# MINI_SAM_D51_013.net
KiCad netlist of a schematic drawn in EAGLE
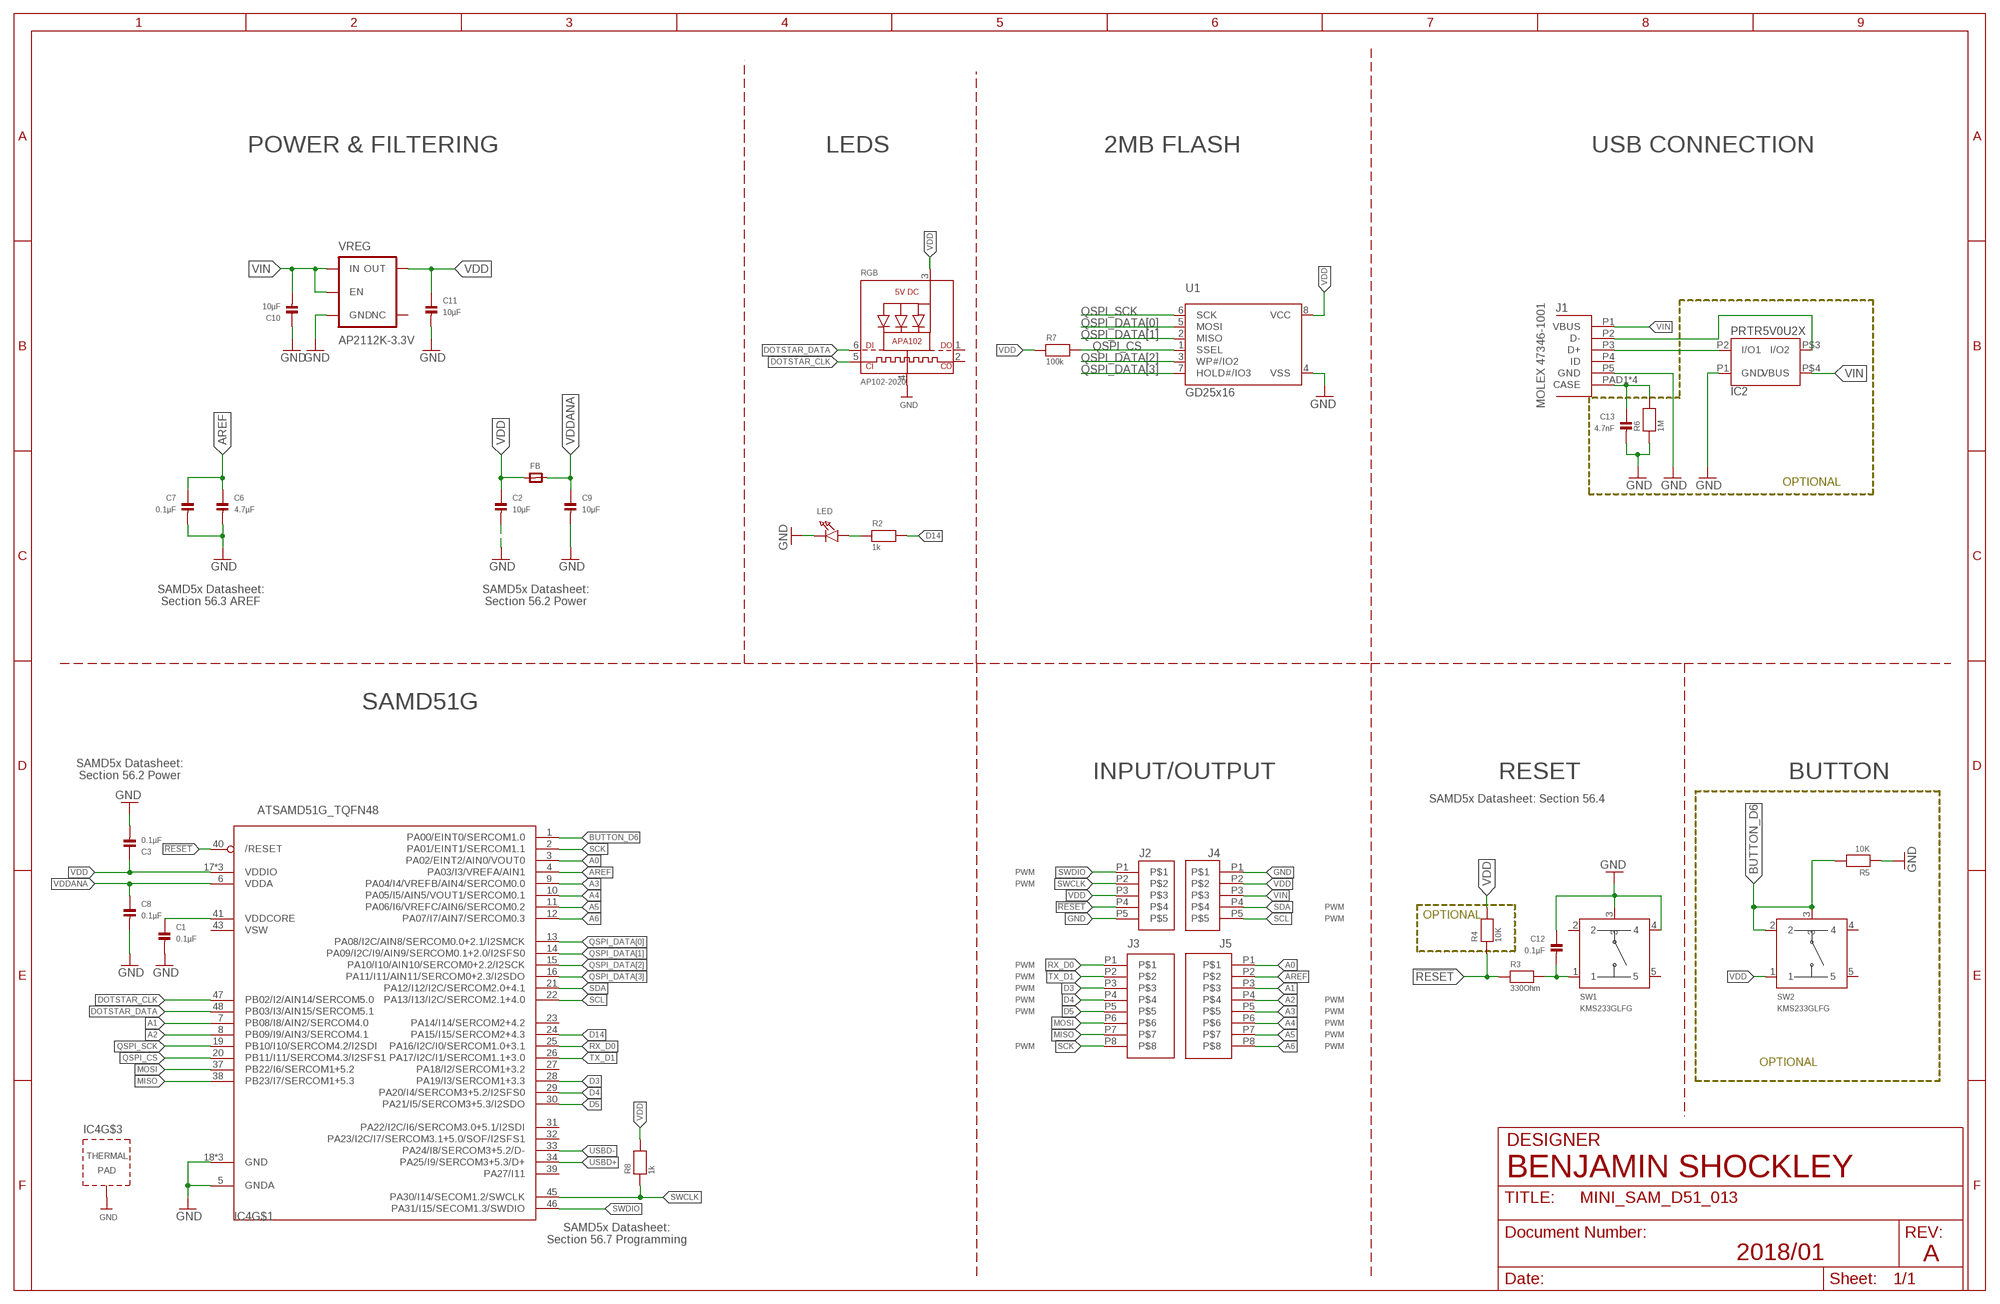
[diagram p0: schematic, sheet 1]

(export (version "E")
  (design (tool "Eeschema 10.0.6"))
  (components
    (comp (ref "C1")
      (value "0.1µF")
      (footprint "eagle-import:_0603MP")
      (libsource (lib "eagle-import") (part "CAP_CERAMIC_0603MP"))
    )
    (comp (ref "C2")
      (value "10µF")
      (footprint "eagle-import:_0603MP")
      (libsource (lib "eagle-import") (part "CAP_CERAMIC_0603MP"))
    )
    (comp (ref "C3")
      (value "0.1µF")
      (footprint "eagle-import:_0603MP")
      (libsource (lib "eagle-import") (part "CAP_CERAMIC_0603MP"))
    )
    (comp (ref "C6")
      (value "4.7µF")
      (footprint "eagle-import:_0603MP")
      (libsource (lib "eagle-import") (part "CAP_CERAMIC_0603MP"))
    )
    (comp (ref "C7")
      (value "0.1µF")
      (footprint "eagle-import:_0603MP")
      (libsource (lib "eagle-import") (part "CAP_CERAMIC_0603MP"))
    )
    (comp (ref "C8")
      (value "0.1µF")
      (footprint "eagle-import:_0603MP")
      (libsource (lib "eagle-import") (part "CAP_CERAMIC_0603MP"))
    )
    (comp (ref "C9")
      (value "10µF")
      (footprint "eagle-import:_0603MP")
      (libsource (lib "eagle-import") (part "CAP_CERAMIC_0603MP"))
    )
    (comp (ref "C10")
      (value "10µF")
      (footprint "eagle-import:_0603MP")
      (libsource (lib "eagle-import") (part "CAP_CERAMIC_0603MP"))
    )
    (comp (ref "C11")
      (value "10µF")
      (footprint "eagle-import:_0603MP")
      (libsource (lib "eagle-import") (part "CAP_CERAMIC_0603MP"))
    )
    (comp (ref "C12")
      (value "0.1µF")
      (footprint "eagle-import:_0603MP")
      (libsource (lib "eagle-import") (part "CAP_CERAMIC_0603MP"))
    )
    (comp (ref "C13")
      (value "4.7nF")
      (footprint "eagle-import:_0603MP")
      (libsource (lib "eagle-import") (part "CAP_CERAMIC_0603MP"))
    )
    (comp (ref "FB")
      (value "FERRITE_0603MP")
      (footprint "eagle-import:_0603MP")
      (libsource (lib "eagle-import") (part "FERRITE_0603MP"))
    )
    (comp (ref "IC2")
      (value "PRTR5V0U2X")
      (footprint "eagle-import:SOT143B_REFLOW")
      (libsource (lib "eagle-import") (part "PRTR5V0U2X"))
    )
    (comp (ref "IC4")
      (value "ATSAMD51G_TQFN48")
      (footprint "eagle-import:TQFN48_7MM")
      (libsource (lib "eagle-import") (part "ATSAMD51G_TQFN48"))
    )
    (comp (ref "J1")
      (value "MOLEX_47346-100147346")
      (footprint "eagle-import:MOLEX_47346-1001")
      (libsource (lib "eagle-import") (part "MOLEX_47346-100147346"))
    )
    (comp (ref "J2")
      (value "1X5_HEADER_1.27MMCAST")
      (footprint "eagle-import:1X5_HEADER_1.27MM_CASTELLATED")
      (libsource (lib "eagle-import") (part "1X5_HEADER_1.27MMCAST"))
    )
    (comp (ref "J3")
      (value "1X8_HEADER_1.27MMCAST")
      (footprint "eagle-import:1X8_HEADER_1.27MM_CASTELLATED")
      (libsource (lib "eagle-import") (part "1X8_HEADER_1.27MMCAST"))
    )
    (comp (ref "J4")
      (value "1X5_HEADER_1.27MMCAST")
      (footprint "eagle-import:1X5_HEADER_1.27MM_CASTELLATED")
      (libsource (lib "eagle-import") (part "1X5_HEADER_1.27MMCAST"))
    )
    (comp (ref "J5")
      (value "1X8_HEADER_1.27MMCAST")
      (footprint "eagle-import:1X8_HEADER_1.27MM_CASTELLATED")
      (libsource (lib "eagle-import") (part "1X8_HEADER_1.27MMCAST"))
    )
    (comp (ref "LED")
      (value "LED0805_NOOUTLINE")
      (footprint "eagle-import:CHIPLED_0805_NOOUTLINE")
      (libsource (lib "eagle-import") (part "LED0805_NOOUTLINE"))
    )
    (comp (ref "R2")
      (value "1k")
      (footprint "eagle-import:_0603MP")
      (libsource (lib "eagle-import") (part "RESISTOR_0603MP"))
    )
    (comp (ref "R3")
      (value "330Ohm")
      (footprint "eagle-import:_0603MP")
      (libsource (lib "eagle-import") (part "RESISTOR_0603MP"))
    )
    (comp (ref "R4")
      (value "10K")
      (footprint "eagle-import:_0603MP")
      (libsource (lib "eagle-import") (part "RESISTOR_0603MP"))
    )
    (comp (ref "R5")
      (value "10K")
      (footprint "eagle-import:_0603MP")
      (libsource (lib "eagle-import") (part "RESISTOR_0603MP"))
    )
    (comp (ref "R6")
      (value "1M")
      (footprint "eagle-import:_0603MP")
      (libsource (lib "eagle-import") (part "RESISTOR_0603MP"))
    )
    (comp (ref "R7")
      (value "100k")
      (footprint "eagle-import:_0603MP")
      (libsource (lib "eagle-import") (part "RESISTOR_0603MP"))
    )
    (comp (ref "R8")
      (value "1k")
      (footprint "eagle-import:_0603MP")
      (libsource (lib "eagle-import") (part "RESISTOR_0603MP"))
    )
    (comp (ref "RGB")
      (value "AP102-2020")
      (footprint "eagle-import:APA102_2020")
      (libsource (lib "eagle-import") (part "APA1022020"))
    )
    (comp (ref "SW1")
      (value "KMS233GLFG")
      (footprint "eagle-import:KMS_SWITCH")
      (libsource (lib "eagle-import") (part "KMS_SWITCHKMS"))
    )
    (comp (ref "SW2")
      (value "KMS233GLFG")
      (footprint "eagle-import:KMS_SWITCH")
      (libsource (lib "eagle-import") (part "KMS_SWITCHKMS"))
    )
    (comp (ref "U1")
      (value "GD25x16")
      (footprint "eagle-import:USON8")
      (libsource (lib "eagle-import") (part "SPIFLASH_8PINUX"))
    )
    (comp (ref "VREG")
      (value "AP2112K-3.3V")
      (footprint "eagle-import:SOT23-5")
      (libsource (lib "eagle-import") (part "V_REG_AP2112K-3.3V"))
    )
  )
  (nets
    (net (code "1") (name "/VSW") (class "Default")
      (node (ref "IC4") (pin "43") (pinfunction "VSW_43") (pintype "power_in"))
    )
    (net (code "2") (name "/~{RESET}") (class "Default")
      (node (ref "IC4") (pin "40") (pinfunction "/RESET_40") (pintype "bidirectional"))
      (node (ref "J2") (pin "P4") (pinfunction "P$4_P4") (pintype "bidirectional"))
      (node (ref "R3") (pin "1") (pinfunction "1_1") (pintype "passive"))
      (node (ref "R4") (pin "1") (pinfunction "1_1") (pintype "passive"))
    )
    (net (code "3") (name "A0") (class "Default")
      (node (ref "IC4") (pin "3") (pinfunction "PA02/EINT2/AIN0/VOUT0_3") (pintype "bidirectional"))
      (node (ref "J5") (pin "P1") (pinfunction "P$1_P1") (pintype "bidirectional"))
    )
    (net (code "4") (name "A1") (class "Default")
      (node (ref "IC4") (pin "7") (pinfunction "PB08/I8/AIN2/SERCOM4.0_7") (pintype "bidirectional"))
      (node (ref "J5") (pin "P3") (pinfunction "P$3_P3") (pintype "bidirectional"))
    )
    (net (code "5") (name "A2") (class "Default")
      (node (ref "IC4") (pin "8") (pinfunction "PB09/I9/AIN3/SERCOM4.1_8") (pintype "bidirectional"))
      (node (ref "J5") (pin "P4") (pinfunction "P$4_P4") (pintype "bidirectional"))
    )
    (net (code "6") (name "A3") (class "Default")
      (node (ref "IC4") (pin "9") (pinfunction "PA04/I4/VREFB/AIN4/SERCOM0.0_9") (pintype "bidirectional"))
      (node (ref "J5") (pin "P5") (pinfunction "P$5_P5") (pintype "bidirectional"))
    )
    (net (code "7") (name "A4") (class "Default")
      (node (ref "IC4") (pin "10") (pinfunction "PA05/I5/AIN5/VOUT1/SERCOM0.1_10") (pintype "bidirectional"))
      (node (ref "J5") (pin "P6") (pinfunction "P$6_P6") (pintype "bidirectional"))
    )
    (net (code "8") (name "A5") (class "Default")
      (node (ref "IC4") (pin "11") (pinfunction "PA06/I6/VREFC/AIN6/SERCOM0.2_11") (pintype "bidirectional"))
      (node (ref "J5") (pin "P7") (pinfunction "P$7_P7") (pintype "bidirectional"))
    )
    (net (code "9") (name "A6") (class "Default")
      (node (ref "IC4") (pin "12") (pinfunction "PA07/I7/AIN7/SERCOM0.3_12") (pintype "bidirectional"))
      (node (ref "J5") (pin "P8") (pinfunction "P$8_P8") (pintype "bidirectional"))
    )
    (net (code "10") (name "AREF") (class "Default")
      (node (ref "C6") (pin "1") (pinfunction "P$1_1") (pintype "passive"))
      (node (ref "C7") (pin "1") (pinfunction "P$1_1") (pintype "passive"))
      (node (ref "IC4") (pin "4") (pinfunction "PA03/I3/VREFA/AIN1_4") (pintype "bidirectional"))
      (node (ref "J5") (pin "P2") (pinfunction "P$2_P2") (pintype "bidirectional"))
    )
    (net (code "11") (name "BUTTON_D6") (class "Default")
      (node (ref "IC4") (pin "1") (pinfunction "PA00/EINT0/SERCOM1.0_1") (pintype "bidirectional"))
      (node (ref "R5") (pin "2") (pinfunction "2_2") (pintype "passive"))
      (node (ref "SW2") (pin "2") (pinfunction "2_2") (pintype "bidirectional"))
      (node (ref "SW2") (pin "3") (pinfunction "3_3") (pintype "bidirectional"))
    )
    (net (code "12") (name "D3") (class "Default")
      (node (ref "IC4") (pin "28") (pinfunction "PA19/I3/SERCOM1+3.3_28") (pintype "bidirectional"))
      (node (ref "J3") (pin "P3") (pinfunction "P$3_P3") (pintype "bidirectional"))
    )
    (net (code "13") (name "D4") (class "Default")
      (node (ref "IC4") (pin "29") (pinfunction "PA20/I4/SERCOM3+5.2/I2SFS0_29") (pintype "bidirectional"))
      (node (ref "J3") (pin "P4") (pinfunction "P$4_P4") (pintype "bidirectional"))
    )
    (net (code "14") (name "D5") (class "Default")
      (node (ref "IC4") (pin "30") (pinfunction "PA21/I5/SERCOM3+5.3/I2SDO_30") (pintype "bidirectional"))
      (node (ref "J3") (pin "P5") (pinfunction "P$5_P5") (pintype "bidirectional"))
    )
    (net (code "15") (name "D14") (class "Default")
      (node (ref "IC4") (pin "24") (pinfunction "PA15/I15/SERCOM2+4.3_24") (pintype "bidirectional"))
      (node (ref "R2") (pin "2") (pinfunction "2_2") (pintype "passive"))
    )
    (net (code "16") (name "DOTSTAR_CLK") (class "Default")
      (node (ref "IC4") (pin "47") (pinfunction "PB02/I2/AIN14/SERCOM5.0_47") (pintype "bidirectional"))
      (node (ref "RGB") (pin "5") (pinfunction "CKI_5") (pintype "input"))
    )
    (net (code "17") (name "DOTSTAR_DATA") (class "Default")
      (node (ref "IC4") (pin "48") (pinfunction "PB03/I3/AIN15/SERCOM5.1_48") (pintype "bidirectional"))
      (node (ref "RGB") (pin "6") (pinfunction "DI_6") (pintype "input"))
    )
    (net (code "18") (name "GND") (class "Default")
      (node (ref "C1") (pin "2") (pinfunction "P$2_2") (pintype "passive"))
      (node (ref "C10") (pin "1") (pinfunction "P$1_1") (pintype "passive"))
      (node (ref "C11") (pin "2") (pinfunction "P$2_2") (pintype "passive"))
      (node (ref "C12") (pin "1") (pinfunction "P$1_1") (pintype "passive"))
      (node (ref "C13") (pin "2") (pinfunction "P$2_2") (pintype "passive"))
      (node (ref "C2") (pin "2") (pinfunction "P$2_2") (pintype "passive"))
      (node (ref "C3") (pin "2") (pinfunction "P$2_2") (pintype "passive"))
      (node (ref "C6") (pin "2") (pinfunction "P$2_2") (pintype "passive"))
      (node (ref "C7") (pin "2") (pinfunction "P$2_2") (pintype "passive"))
      (node (ref "C8") (pin "2") (pinfunction "P$2_2") (pintype "passive"))
      (node (ref "C9") (pin "2") (pinfunction "P$2_2") (pintype "passive"))
      (node (ref "IC2") (pin "P1") (pinfunction "GND_P1") (pintype "bidirectional"))
      (node (ref "IC4") (pin "18") (pinfunction "GND_18") (pintype "power_in"))
      (node (ref "IC4") (pin "35") (pinfunction "GND_35") (pintype "power_in"))
      (node (ref "IC4") (pin "42") (pinfunction "GND_42") (pintype "power_in"))
      (node (ref "IC4") (pin "5") (pinfunction "GNDA_5") (pintype "power_in"))
      (node (ref "IC4") (pin "THERMAL") (pinfunction "TP_THERMAL") (pintype "power_in"))
      (node (ref "J1") (pin "P5") (pinfunction "GND_P5") (pintype "power_in"))
      (node (ref "J2") (pin "P5") (pinfunction "P$5_P5") (pintype "bidirectional"))
      (node (ref "J4") (pin "P1") (pinfunction "P$1_P1") (pintype "bidirectional"))
      (node (ref "LED") (pin "C") (pinfunction "C_C") (pintype "passive"))
      (node (ref "R5") (pin "1") (pinfunction "1_1") (pintype "passive"))
      (node (ref "R6") (pin "1") (pinfunction "1_1") (pintype "passive"))
      (node (ref "RGB") (pin "4") (pinfunction "GND_4") (pintype "power_in"))
      (node (ref "SW1") (pin "3") (pinfunction "3_3") (pintype "bidirectional"))
      (node (ref "SW1") (pin "4") (pinfunction "4_4") (pintype "bidirectional"))
      (node (ref "U1") (pin "4") (pinfunction "VSS_4") (pintype "bidirectional"))
      (node (ref "VREG") (pin "2") (pinfunction "GND_2") (pintype "input"))
    )
    (net (code "19") (name "MISO") (class "Default")
      (node (ref "IC4") (pin "38") (pinfunction "PB23/I7/SERCOM1+5.3_38") (pintype "bidirectional"))
      (node (ref "J3") (pin "P7") (pinfunction "P$7_P7") (pintype "bidirectional"))
    )
    (net (code "20") (name "MOSI") (class "Default")
      (node (ref "IC4") (pin "37") (pinfunction "PB22/I6/SERCOM1+5.2_37") (pintype "bidirectional"))
      (node (ref "J3") (pin "P6") (pinfunction "P$6_P6") (pintype "bidirectional"))
    )
    (net (code "21") (name "Net-(C1-P$1)") (class "Default")
      (node (ref "C1") (pin "1") (pinfunction "P$1_1") (pintype "passive"))
      (node (ref "IC4") (pin "41") (pinfunction "VDDCORE_41") (pintype "power_in"))
    )
    (net (code "22") (name "Net-(C12-P$2)") (class "Default")
      (node (ref "C12") (pin "2") (pinfunction "P$2_2") (pintype "passive"))
      (node (ref "R3") (pin "2") (pinfunction "2_2") (pintype "passive"))
      (node (ref "SW1") (pin "1") (pinfunction "1_1") (pintype "bidirectional"))
    )
    (net (code "23") (name "Net-(C13-P$1)") (class "Default")
      (node (ref "C13") (pin "1") (pinfunction "P$1_1") (pintype "passive"))
      (node (ref "J1") (pin "PAD1") (pinfunction "CASE_PAD1") (pintype "bidirectional"))
      (node (ref "J1") (pin "PAD2") (pinfunction "CASE_PAD2") (pintype "bidirectional"))
      (node (ref "J1") (pin "PAD3") (pinfunction "CASE_PAD3") (pintype "bidirectional"))
      (node (ref "J1") (pin "PAD4") (pinfunction "CASE_PAD4") (pintype "bidirectional"))
      (node (ref "R6") (pin "2") (pinfunction "2_2") (pintype "passive"))
    )
    (net (code "24") (name "Net-(LED-PadA)") (class "Default")
      (node (ref "LED") (pin "A") (pinfunction "A_A") (pintype "passive"))
      (node (ref "R2") (pin "1") (pinfunction "1_1") (pintype "passive"))
    )
    (net (code "25") (name "QSPI_CS") (class "Default")
      (node (ref "IC4") (pin "20") (pinfunction "PB11/I11/SERCOM4.3/I2SFS1_20") (pintype "bidirectional"))
      (node (ref "R7") (pin "2") (pinfunction "2_2") (pintype "passive"))
      (node (ref "U1") (pin "1") (pinfunction "SSEL_1") (pintype "bidirectional"))
    )
    (net (code "26") (name "QSPI_DATA[0]") (class "Default")
      (node (ref "IC4") (pin "13") (pinfunction "PA08/I2C/AIN8/SERCOM0.0+2.1/I2SMCK_13") (pintype "bidirectional"))
      (node (ref "U1") (pin "5") (pinfunction "MOSI_5") (pintype "bidirectional"))
    )
    (net (code "27") (name "QSPI_DATA[1]") (class "Default")
      (node (ref "IC4") (pin "14") (pinfunction "PA09/I2C/I9/AIN9/SERCOM0.1+2.0/I2SFS0_14") (pintype "bidirectional"))
      (node (ref "U1") (pin "2") (pinfunction "MISO_2") (pintype "bidirectional"))
    )
    (net (code "28") (name "QSPI_DATA[2]") (class "Default")
      (node (ref "IC4") (pin "15") (pinfunction "PA10/I10/AIN10/SERCOM0+2.2/I2SCK_15") (pintype "bidirectional"))
      (node (ref "U1") (pin "3") (pinfunction "WP#/IO2_3") (pintype "bidirectional"))
    )
    (net (code "29") (name "QSPI_DATA[3]") (class "Default")
      (node (ref "IC4") (pin "16") (pinfunction "PA11/I11/AIN11/SERCOM0+2.3/I2SDO_16") (pintype "bidirectional"))
      (node (ref "U1") (pin "7") (pinfunction "HOLD#/IO3_7") (pintype "bidirectional"))
    )
    (net (code "30") (name "QSPI_SCK") (class "Default")
      (node (ref "IC4") (pin "19") (pinfunction "PB10/I10/SERCOM4.2/I2SDI_19") (pintype "bidirectional"))
      (node (ref "U1") (pin "6") (pinfunction "SCK_6") (pintype "bidirectional"))
    )
    (net (code "31") (name "RX_D0") (class "Default")
      (node (ref "IC4") (pin "25") (pinfunction "PA16/I2C/I0/SERCOM1.0+3.1_25") (pintype "bidirectional"))
      (node (ref "J3") (pin "P1") (pinfunction "P$1_P1") (pintype "bidirectional"))
    )
    (net (code "32") (name "SCK") (class "Default")
      (node (ref "IC4") (pin "2") (pinfunction "PA01/EINT1/SERCOM1.1_2") (pintype "bidirectional"))
      (node (ref "J3") (pin "P8") (pinfunction "P$8_P8") (pintype "bidirectional"))
    )
    (net (code "33") (name "SCL") (class "Default")
      (node (ref "IC4") (pin "22") (pinfunction "PA13/I13/I2C/SERCOM2.1+4.0_22") (pintype "bidirectional"))
      (node (ref "J4") (pin "P5") (pinfunction "P$5_P5") (pintype "bidirectional"))
    )
    (net (code "34") (name "SDA") (class "Default")
      (node (ref "IC4") (pin "21") (pinfunction "PA12/I12/I2C/SERCOM2.0+4.1_21") (pintype "bidirectional"))
      (node (ref "J4") (pin "P4") (pinfunction "P$4_P4") (pintype "bidirectional"))
    )
    (net (code "35") (name "SWCLK") (class "Default")
      (node (ref "IC4") (pin "45") (pinfunction "PA30/I14/SECOM1.2/SWCLK_45") (pintype "bidirectional"))
      (node (ref "J2") (pin "P2") (pinfunction "P$2_P2") (pintype "bidirectional"))
      (node (ref "R8") (pin "1") (pinfunction "1_1") (pintype "passive"))
    )
    (net (code "36") (name "SWDIO") (class "Default")
      (node (ref "IC4") (pin "46") (pinfunction "PA31/I15/SECOM1.3/SWDIO_46") (pintype "bidirectional"))
      (node (ref "J2") (pin "P1") (pinfunction "P$1_P1") (pintype "bidirectional"))
    )
    (net (code "37") (name "TX_D1") (class "Default")
      (node (ref "IC4") (pin "26") (pinfunction "PA17/I2C/I1/SERCOM1.1+3.0_26") (pintype "bidirectional"))
      (node (ref "J3") (pin "P2") (pinfunction "P$2_P2") (pintype "bidirectional"))
    )
    (net (code "38") (name "USBD+") (class "Default")
      (node (ref "IC2") (pin "P2") (pinfunction "I/O1_P2") (pintype "bidirectional"))
      (node (ref "IC4") (pin "34") (pinfunction "PA25/I9/SERCOM3+5.3/D+_34") (pintype "bidirectional"))
      (node (ref "J1") (pin "P3") (pinfunction "D+_P3") (pintype "bidirectional"))
    )
    (net (code "39") (name "USBD-") (class "Default")
      (node (ref "IC2") (pin "P$3") (pinfunction "I/O2_P$3") (pintype "bidirectional"))
      (node (ref "IC4") (pin "33") (pinfunction "PA24/I8/SERCOM3+5.2/D-_33") (pintype "bidirectional"))
      (node (ref "J1") (pin "P2") (pinfunction "D-_P2") (pintype "bidirectional"))
    )
    (net (code "40") (name "VDD") (class "Default")
      (node (ref "C11") (pin "1") (pinfunction "P$1_1") (pintype "passive"))
      (node (ref "C2") (pin "1") (pinfunction "P$1_1") (pintype "passive"))
      (node (ref "C3") (pin "1") (pinfunction "P$1_1") (pintype "passive"))
      (node (ref "FB") (pin "1") (pinfunction "P$1_1") (pintype "passive"))
      (node (ref "IC4") (pin "17") (pinfunction "VDDIO_17") (pintype "power_in"))
      (node (ref "IC4") (pin "36") (pinfunction "VDDIO_36") (pintype "power_in"))
      (node (ref "IC4") (pin "44") (pinfunction "VDDIO_44") (pintype "power_in"))
      (node (ref "J2") (pin "P3") (pinfunction "P$3_P3") (pintype "bidirectional"))
      (node (ref "J4") (pin "P2") (pinfunction "P$2_P2") (pintype "bidirectional"))
      (node (ref "R4") (pin "2") (pinfunction "2_2") (pintype "passive"))
      (node (ref "R7") (pin "1") (pinfunction "1_1") (pintype "passive"))
      (node (ref "R8") (pin "2") (pinfunction "2_2") (pintype "passive"))
      (node (ref "RGB") (pin "3") (pinfunction "VDD_3") (pintype "power_in"))
      (node (ref "SW2") (pin "1") (pinfunction "1_1") (pintype "bidirectional"))
      (node (ref "U1") (pin "8") (pinfunction "VCC_8") (pintype "bidirectional"))
      (node (ref "VREG") (pin "5") (pinfunction "OUT_5") (pintype "passive"))
    )
    (net (code "41") (name "VDDANA") (class "Default")
      (node (ref "C8") (pin "1") (pinfunction "P$1_1") (pintype "passive"))
      (node (ref "C9") (pin "1") (pinfunction "P$1_1") (pintype "passive"))
      (node (ref "FB") (pin "2") (pinfunction "P$2_2") (pintype "passive"))
      (node (ref "IC4") (pin "6") (pinfunction "VDDA_6") (pintype "power_in"))
    )
    (net (code "42") (name "VIN") (class "Default")
      (node (ref "C10") (pin "2") (pinfunction "P$2_2") (pintype "passive"))
      (node (ref "IC2") (pin "P$4") (pinfunction "VBUS_P$4") (pintype "bidirectional"))
      (node (ref "J1") (pin "P1") (pinfunction "VBUS_P1") (pintype "power_in"))
      (node (ref "J4") (pin "P3") (pinfunction "P$3_P3") (pintype "bidirectional"))
      (node (ref "VREG") (pin "1") (pinfunction "IN_1") (pintype "input"))
      (node (ref "VREG") (pin "3") (pinfunction "EN_3") (pintype "input"))
    )
    (net (code "43") (name "unconnected-(IC4A-PA14{slash}I14{slash}SERCOM2+4.2-Pad23)") (class "Default")
      (node (ref "IC4") (pin "23") (pinfunction "PA14/I14/SERCOM2+4.2_23") (pintype "bidirectional"))
    )
    (net (code "44") (name "unconnected-(IC4A-PA18{slash}I2{slash}SERCOM1+3.2-Pad27)") (class "Default")
      (node (ref "IC4") (pin "27") (pinfunction "PA18/I2/SERCOM1+3.2_27") (pintype "bidirectional"))
    )
    (net (code "45") (name "unconnected-(IC4A-PA22{slash}I2C{slash}I6{slash}SERCOM3.0+5.1{slash}I2SDI-Pad31)") (class "Default")
      (node (ref "IC4") (pin "31") (pinfunction "PA22/I2C/I6/SERCOM3.0+5.1/I2SDI_31") (pintype "bidirectional"))
    )
    (net (code "46") (name "unconnected-(IC4A-PA23{slash}I2C{slash}I7{slash}SERCOM3.1+5.0{slash}SOF{slash}I2SFS1-Pad32)") (class "Default")
      (node (ref "IC4") (pin "32") (pinfunction "PA23/I2C/I7/SERCOM3.1+5.0/SOF/I2SFS1_32") (pintype "bidirectional"))
    )
    (net (code "47") (name "unconnected-(IC4A-PA27{slash}I11-Pad39)") (class "Default")
      (node (ref "IC4") (pin "39") (pinfunction "PA27/I11_39") (pintype "bidirectional"))
    )
    (net (code "48") (name "unconnected-(J1-ID-PadP4)") (class "Default")
      (node (ref "J1") (pin "P4") (pinfunction "ID_P4") (pintype "bidirectional"))
    )
    (net (code "49") (name "unconnected-(RGB-CKO-Pad2)") (class "Default")
      (node (ref "RGB") (pin "2") (pinfunction "CKO_2") (pintype "output"))
    )
    (net (code "50") (name "unconnected-(RGB-DO-Pad1)") (class "Default")
      (node (ref "RGB") (pin "1") (pinfunction "DO_1") (pintype "output"))
    )
    (net (code "51") (name "unconnected-(SW1-Pad2)") (class "Default")
      (node (ref "SW1") (pin "2") (pinfunction "2_2") (pintype "bidirectional"))
    )
    (net (code "52") (name "unconnected-(SW1-Pad5)") (class "Default")
      (node (ref "SW1") (pin "5") (pinfunction "5_5") (pintype "bidirectional"))
    )
    (net (code "53") (name "unconnected-(SW2-Pad4)") (class "Default")
      (node (ref "SW2") (pin "4") (pinfunction "4_4") (pintype "bidirectional"))
    )
    (net (code "54") (name "unconnected-(SW2-Pad5)") (class "Default")
      (node (ref "SW2") (pin "5") (pinfunction "5_5") (pintype "bidirectional"))
    )
    (net (code "55") (name "unconnected-(VREG-NC-Pad4)") (class "Default")
      (node (ref "VREG") (pin "4") (pinfunction "NC_4") (pintype "input"))
    )
  )
)
